# SparkFun_LS20126-Breakout-v11.net
KiCad netlist of a schematic drawn in EAGLE
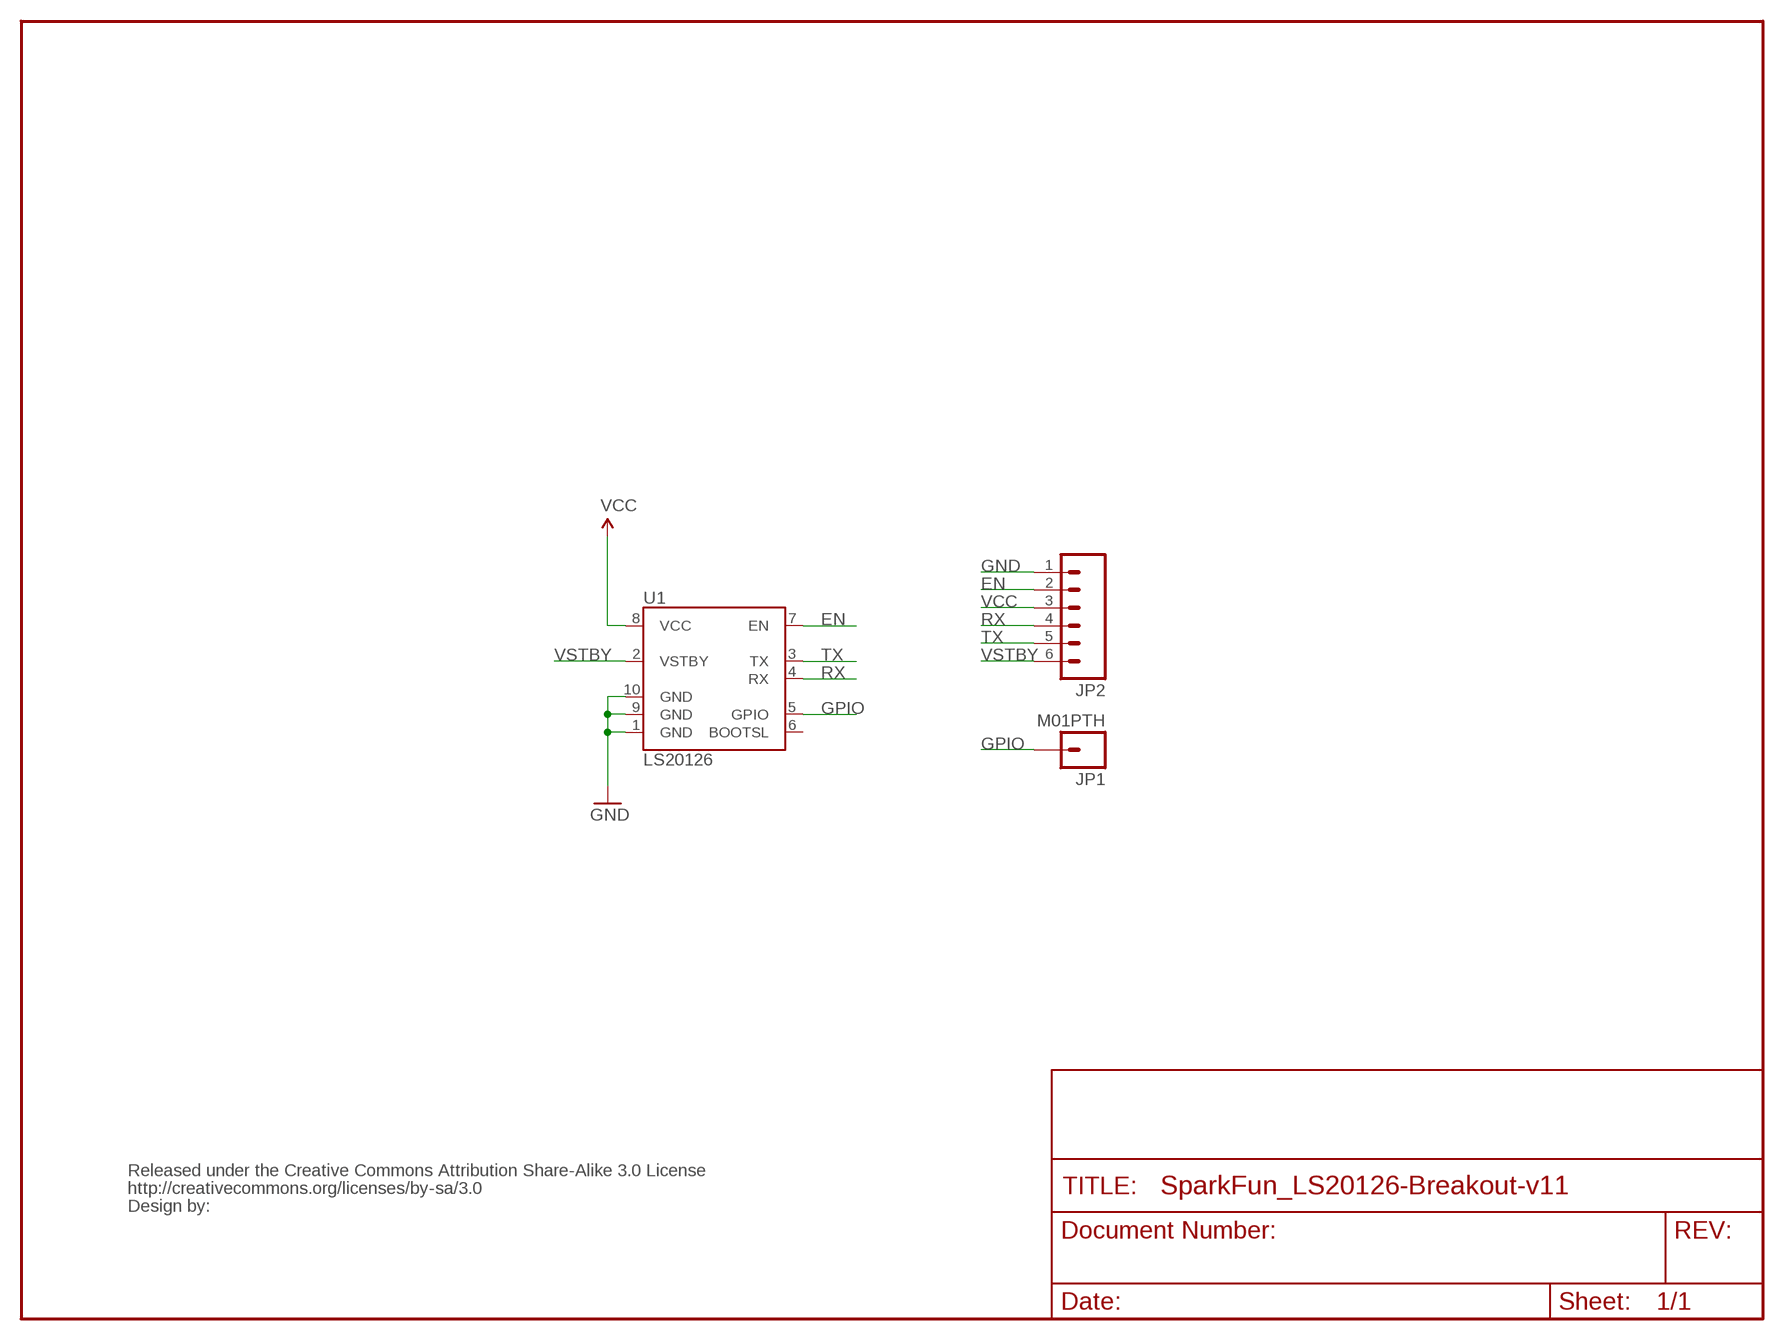
[diagram p0: schematic, sheet 1]

(export (version "E")
  (design (tool "Eeschema 10.0.6"))
  (components
    (comp (ref "JP1")
      (value "M01PTH")
      (footprint "eagle-import:1X01")
      (libsource (lib "eagle-import") (part "M01PTH"))
    )
    (comp (ref "JP2")
      (value "M06SIP")
      (footprint "eagle-import:1X06")
      (libsource (lib "eagle-import") (part "M06SIP"))
    )
    (comp (ref "U$1")
      (value "CREATIVE_COMMONS")
      (footprint "eagle-import:CREATIVE_COMMONS")
      (libsource (lib "eagle-import") (part "CREATIVE_COMMONS"))
    )
    (comp (ref "U1")
      (value "LS20126")
      (footprint "eagle-import:LS20126")
      (libsource (lib "eagle-import") (part "LS20126"))
    )
  )
  (nets
    (net (code "1") (name "/EN") (class "Default")
      (node (ref "JP2") (pin "2") (pinfunction "2_2") (pintype "passive"))
      (node (ref "U1") (pin "7") (pinfunction "EN_7") (pintype "bidirectional"))
    )
    (net (code "2") (name "/GPIO") (class "Default")
      (node (ref "JP1") (pin "1") (pinfunction "1_1") (pintype "passive"))
      (node (ref "U1") (pin "5") (pinfunction "GPIO_5") (pintype "bidirectional"))
    )
    (net (code "3") (name "/RX") (class "Default")
      (node (ref "JP2") (pin "4") (pinfunction "4_4") (pintype "passive"))
      (node (ref "U1") (pin "4") (pinfunction "RX_4") (pintype "bidirectional"))
    )
    (net (code "4") (name "/TX") (class "Default")
      (node (ref "JP2") (pin "5") (pinfunction "5_5") (pintype "passive"))
      (node (ref "U1") (pin "3") (pinfunction "TX_3") (pintype "bidirectional"))
    )
    (net (code "5") (name "/VSTBY") (class "Default")
      (node (ref "JP2") (pin "6") (pinfunction "6_6") (pintype "passive"))
      (node (ref "U1") (pin "2") (pinfunction "VSTBY_2") (pintype "bidirectional"))
    )
    (net (code "6") (name "GND") (class "Default")
      (node (ref "JP2") (pin "1") (pinfunction "1_1") (pintype "passive"))
      (node (ref "U1") (pin "1") (pinfunction "GND_1") (pintype "bidirectional"))
      (node (ref "U1") (pin "10") (pinfunction "GND_10") (pintype "bidirectional"))
      (node (ref "U1") (pin "9") (pinfunction "GND_9") (pintype "bidirectional"))
    )
    (net (code "7") (name "VCC") (class "Default")
      (node (ref "JP2") (pin "3") (pinfunction "3_3") (pintype "passive"))
      (node (ref "U1") (pin "8") (pinfunction "VCC_8") (pintype "bidirectional"))
    )
    (net (code "8") (name "unconnected-(U1-BOOTSL-Pad6)") (class "Default")
      (node (ref "U1") (pin "6") (pinfunction "BOOTSL_6") (pintype "bidirectional"))
    )
  )
)
